# PDS_LogicConnections.net
KiCad netlist of a schematic drawn in Altium Designer
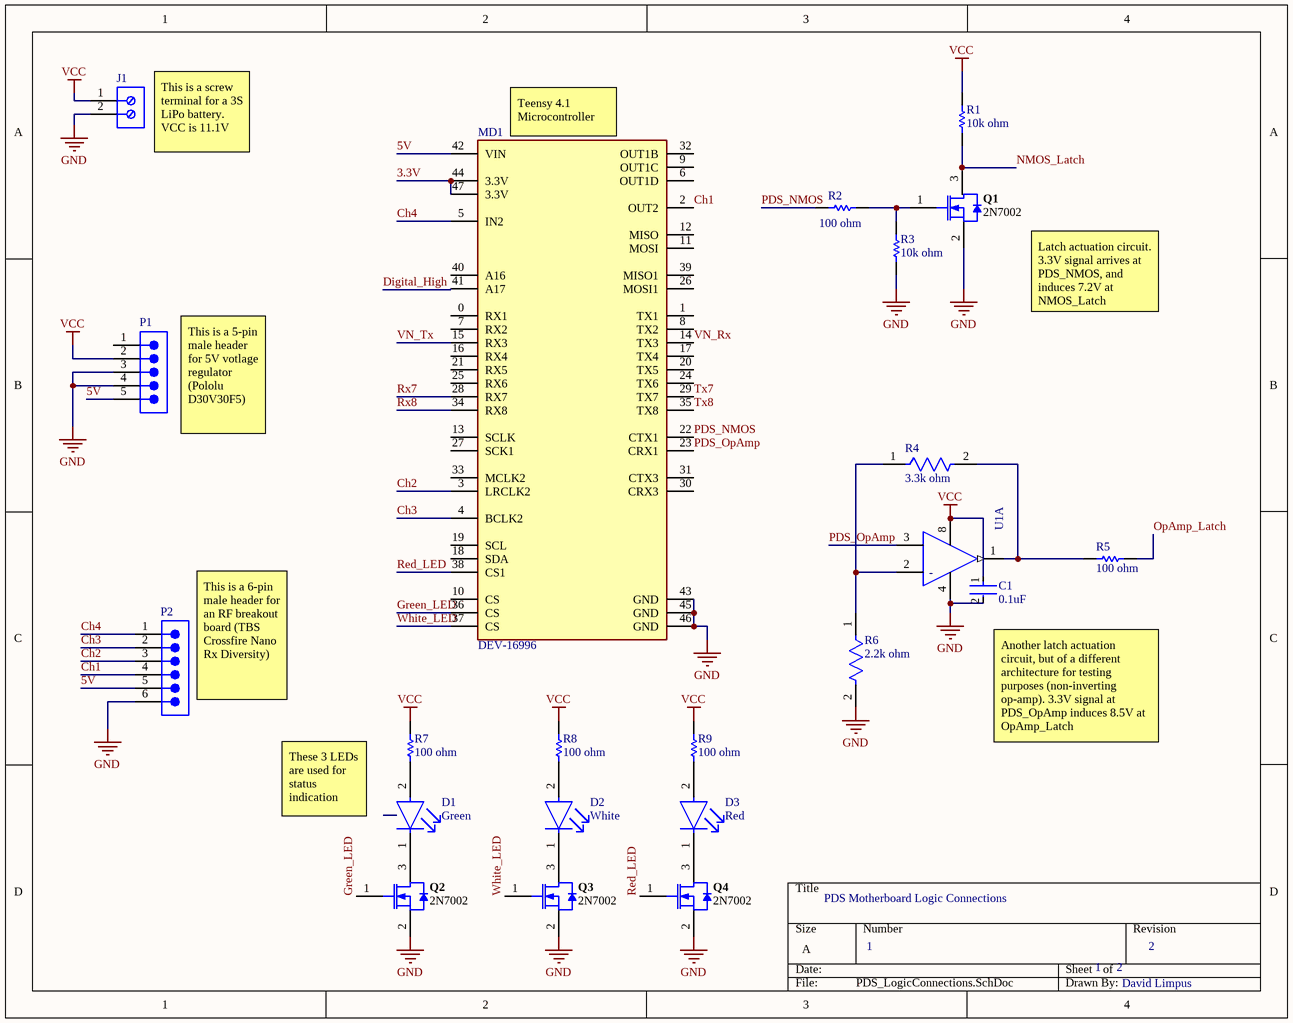
[diagram p0: PDS_LogicConnections.SchDoc]

(export (version "E")
  (design (tool "Eeschema 10.0.6"))
  (components
    (comp (ref "C1")
      (value "0.1uF")
      (footprint "FP-C0603C-CF-MFG")
      (description "CAP CER 0.1UF 50V X7R 0603")
      (fields (field (name "TOLERANCE") "0.1") (field (name "MANUFACTURER") "KEMET"))
      (libsource (lib "Altium Content Vault") (part "b4654b650e69147ec39a6b967a45e02"))
    )
    (comp (ref "D1")
      (value "Green")
      (footprint "FP-LTST-C190GKT-MFG")
      (description "LED GREEN CLEAR CHIP SMD")
      (fields (field (name "VOLTAGE") "2V"))
      (libsource (lib "Altium Content Vault") (part "8706943c75ba83719d021d2fdc84c58"))
    )
    (comp (ref "D2")
      (value "White")
      (footprint "FP-LTW-C191DS5-MFG")
      (description "LED WHITE CHIP SMD")
      (fields
        (field (name "OCTOPART") "https://octopart.com/ltw-c191ds5-lite-on-9287539")
        (field (name "MANUFACTURER PART NUMBER") "LTW-C191DS5")
      )
      (libsource (lib "Altium Content Vault") (part "8706943c75ba83719d021d2fdc84c58"))
    )
    (comp (ref "D3")
      (value "Red")
      (footprint "FP-LTST-C190EKT-MFG")
      (description "LED RED CLEAR CHIP SMD")
      (libsource (lib "Altium Content Vault") (part "8706943c75ba83719d021d2fdc84c58"))
    )
    (comp (ref "J1")
      (value "1725656")
      (footprint "PHOE-1725656-2")
      (description "Male Header, Pitch 2.54 mm, 1 x 2 Position, Height 9 mm, Tail Length 3.5 mm")
      (fields (field (name "MANUFACTURER") "Phoenix Contact"))
      (libsource (lib "Altium Content Vault") (part "CN-1P-F-TB2"))
    )
    (comp (ref "MD1")
      (value "DEV-16996")
      (footprint "FP-DEV-16996-MFG")
      (description "TEENSY 4.1 (HEADERS)")
      (libsource (lib "Altium Content Vault") (part "080115a1ce54750370cf87ec145ee29"))
    )
    (comp (ref "P1")
      (value "61300511121")
      (footprint "61300511121")
      (libsource (lib "Altium Content Vault") (part "Header_Male_1R_05P"))
    )
    (comp (ref "P2")
      (value "61300611121")
      (footprint "61300611121")
      (libsource (lib "Altium Content Vault") (part "Header_Male_1R_06P"))
    )
    (comp (ref "Q1")
      (value "2N7002")
      (footprint "INF-PG-SOT23_M")
      (fields (field (name "MANUFACTURER") "Infineon"))
      (libsource (lib "") (part "INF-NDMOS-GSD-3_1"))
    )
    (comp (ref "Q2")
      (value "2N7002")
      (footprint "INF-PG-SOT23_M")
      (fields (field (name "MANUFACTURER") "Infineon"))
      (libsource (lib "Altium Content Vault") (part "INF-NDMOS-GSD-3"))
    )
    (comp (ref "Q3")
      (value "2N7002")
      (footprint "INF-PG-SOT23_M")
      (fields (field (name "MANUFACTURER") "Infineon"))
      (libsource (lib "Altium Content Vault") (part "INF-NDMOS-GSD-3"))
    )
    (comp (ref "Q4")
      (value "2N7002")
      (footprint "INF-PG-SOT23_M")
      (fields (field (name "MANUFACTURER") "Infineon"))
      (libsource (lib "Altium Content Vault") (part "INF-NDMOS-GSD-3"))
    )
    (comp (ref "R1")
      (value "10k ohm")
      (footprint "RESC1609X50X30NL8T20")
      (description "Chip Resistor, 10 KOhm, +/- 1%, 100 mW, -55 to 155 degC, 0603 (1608 Metric), RoHS, Tape and Reel")
      (fields (field (name "MANUFACTURER") "Vishay Semiconductor"))
      (libsource (lib "Altium Content Vault") (part "RES-2"))
    )
    (comp (ref "R2")
      (value "100 ohm")
      (footprint "RESC1609X50X30ML8T20")
      (description "Chip Resistor, 100 Ohm, +/- 1%, 100 mW,-55 to 155 degC, 0603 (1608 Metric), RoHS, Tape and Ree")
      (fields (field (name "MANUFACTURER") "Vishay Semiconductor"))
      (libsource (lib "Altium Content Vault") (part "RES-2"))
    )
    (comp (ref "R3")
      (value "10k ohm")
      (footprint "RESC1609X50X30NL8T20")
      (description "Chip Resistor, 10 KOhm, +/- 1%, 100 mW, -55 to 155 degC, 0603 (1608 Metric), RoHS, Tape and Reel")
      (fields (field (name "MANUFACTURER") "Vishay Semiconductor"))
      (libsource (lib "Altium Content Vault") (part "RES-2"))
    )
    (comp (ref "R4")
      (value "3.3k ohm")
      (footprint "FP-RG1608-MFG")
      (description "Automotive Metal Thin Film Chip Resistor, 0603, 3.3kΩ, 0.1%, 25ppm/°C, 0.1W, 100V")
      (fields (field (name "TOLERANCE") "0.1%"))
      (libsource (lib "Altium Content Vault") (part "1029c3af85768c4190bb7ad29bc67b5"))
    )
    (comp (ref "R5")
      (value "100 ohm")
      (footprint "RESC1609X50X30ML8T20")
      (description "Chip Resistor, 100 Ohm, +/- 1%, 100 mW,-55 to 155 degC, 0603 (1608 Metric), RoHS, Tape and Ree")
      (fields (field (name "MANUFACTURER") "Vishay Semiconductor"))
      (libsource (lib "Altium Content Vault") (part "RES-2"))
    )
    (comp (ref "R6")
      (value "2.2k ohm")
      (footprint "FP-RT0603-MFG")
      (description "RES SMD 2.2K OHM 1% 1/10W 0603")
      (fields
        (field (name "MANUFACTURER") "Yageo")
        (field (name "OCTOPART") "https://octopart.com/rt0603fre072k2l-yageo-40019811")
      )
      (libsource (lib "Altium Content Vault") (part "1029c3af85768c4190bb7ad29bc67b5"))
    )
    (comp (ref "R7")
      (value "100 ohm")
      (footprint "RESC1609X50X30ML8T20")
      (description "Chip Resistor, 100 Ohm, +/- 1%, 100 mW,-55 to 155 degC, 0603 (1608 Metric), RoHS, Tape and Ree")
      (fields (field (name "MANUFACTURER") "Vishay Semiconductor"))
      (libsource (lib "Altium Content Vault") (part "RES-2"))
    )
    (comp (ref "R8")
      (value "100 ohm")
      (footprint "RESC1609X50X30ML8T20")
      (description "Chip Resistor, 100 Ohm, +/- 1%, 100 mW,-55 to 155 degC, 0603 (1608 Metric), RoHS, Tape and Ree")
      (fields (field (name "MANUFACTURER") "Vishay Semiconductor"))
      (libsource (lib "Altium Content Vault") (part "RES-2"))
    )
    (comp (ref "R9")
      (value "100 ohm")
      (footprint "RESC1609X50X30ML8T20")
      (description "Chip Resistor, 100 Ohm, +/- 1%, 100 mW,-55 to 155 degC, 0603 (1608 Metric), RoHS, Tape and Ree")
      (fields (field (name "MANUFACTURER") "Vishay Semiconductor"))
      (libsource (lib "Altium Content Vault") (part "RES-2"))
    )
    (comp (ref "U1")
      (value "LM358DR")
      (footprint "FP-D0008A-MFG")
      (description "IC OPAMP GP 2 CIRCUIT 8SOIC")
      (libsource (lib "Altium Content Vault") (part "0afdfe5f461d2cdd85604ff8654be97"))
    )
  )
  (nets
    (net (code "1") (name "/3.3V") (class "Default")
      (node (ref "MD1") (pin "44") (pinfunction "3.3V_44") (pintype "passive"))
      (node (ref "MD1") (pin "47") (pinfunction "3.3V_47") (pintype "passive"))
    )
    (net (code "2") (name "/5V") (class "Default")
      (node (ref "MD1") (pin "42") (pinfunction "VIN_42") (pintype "passive"))
      (node (ref "P1") (pin "5") (pinfunction "5_5") (pintype "passive"))
      (node (ref "P2") (pin "5") (pinfunction "5_5") (pintype "passive"))
    )
    (net (code "3") (name "/Ch1") (class "Default")
      (node (ref "MD1") (pin "2") (pinfunction "OUT2_2") (pintype "passive"))
      (node (ref "P2") (pin "4") (pinfunction "4_4") (pintype "passive"))
    )
    (net (code "4") (name "/Ch2") (class "Default")
      (node (ref "MD1") (pin "3") (pinfunction "LRCLK2_3") (pintype "passive"))
      (node (ref "P2") (pin "3") (pinfunction "3_3") (pintype "passive"))
    )
    (net (code "5") (name "/Ch3") (class "Default")
      (node (ref "MD1") (pin "4") (pinfunction "BCLK2_4") (pintype "passive"))
      (node (ref "P2") (pin "2") (pinfunction "2_2") (pintype "passive"))
    )
    (net (code "6") (name "/Ch4") (class "Default")
      (node (ref "MD1") (pin "5") (pinfunction "IN2_5") (pintype "passive"))
      (node (ref "P2") (pin "1") (pinfunction "1_1") (pintype "passive"))
    )
    (net (code "7") (name "/Digital_High") (class "Default")
      (node (ref "MD1") (pin "41") (pinfunction "A17_41") (pintype "passive"))
    )
    (net (code "8") (name "/Green_LED") (class "Default")
      (node (ref "MD1") (pin "36") (pinfunction "CS_36") (pintype "passive"))
      (node (ref "Q2") (pin "1") (pinfunction "GATE_1") (pintype "passive"))
    )
    (net (code "9") (name "/NMOS_Latch") (class "Default")
      (node (ref "Q1") (pin "3") (pinfunction "DRAIN_3") (pintype "passive"))
      (node (ref "R1") (pin "2") (pinfunction "2_2") (pintype "passive"))
    )
    (net (code "10") (name "/OpAmp_Latch") (class "Default")
      (node (ref "R5") (pin "2") (pinfunction "2_2") (pintype "passive"))
    )
    (net (code "11") (name "/PDS_NMOS") (class "Default")
      (node (ref "MD1") (pin "22") (pinfunction "CTX1_22") (pintype "passive"))
      (node (ref "R2") (pin "1") (pinfunction "1_1") (pintype "passive"))
    )
    (net (code "12") (name "/PDS_OpAmp") (class "Default")
      (node (ref "MD1") (pin "23") (pinfunction "CRX1_23") (pintype "passive"))
      (node (ref "U1") (pin "3") (pinfunction "IN1+_3") (pintype "tri_state"))
    )
    (net (code "13") (name "/Red_LED") (class "Default")
      (node (ref "MD1") (pin "38") (pinfunction "CS1_38") (pintype "passive"))
      (node (ref "Q4") (pin "1") (pinfunction "GATE_1") (pintype "passive"))
    )
    (net (code "14") (name "/Rx7") (class "Default")
      (node (ref "MD1") (pin "28") (pinfunction "RX7_28") (pintype "passive"))
    )
    (net (code "15") (name "/Rx8") (class "Default")
      (node (ref "MD1") (pin "34") (pinfunction "RX8_34") (pintype "passive"))
    )
    (net (code "16") (name "/Tx7") (class "Default")
      (node (ref "MD1") (pin "29") (pinfunction "TX7_29") (pintype "passive"))
    )
    (net (code "17") (name "/Tx8") (class "Default")
      (node (ref "MD1") (pin "35") (pinfunction "TX8_35") (pintype "passive"))
    )
    (net (code "18") (name "/VN_Rx") (class "Default")
      (node (ref "MD1") (pin "14") (pinfunction "TX3_14") (pintype "passive"))
    )
    (net (code "19") (name "/VN_Tx") (class "Default")
      (node (ref "MD1") (pin "15") (pinfunction "RX3_15") (pintype "passive"))
    )
    (net (code "20") (name "/White_LED") (class "Default")
      (node (ref "MD1") (pin "37") (pinfunction "CS_37") (pintype "passive"))
      (node (ref "Q3") (pin "1") (pinfunction "GATE_1") (pintype "passive"))
    )
    (net (code "21") (name "GND") (class "Default")
      (node (ref "C1") (pin "2") (pinfunction "2_2") (pintype "passive"))
      (node (ref "J1") (pin "2") (pinfunction "2_2") (pintype "passive"))
      (node (ref "MD1") (pin "43") (pinfunction "GND_43") (pintype "passive"))
      (node (ref "MD1") (pin "45") (pinfunction "GND_45") (pintype "passive"))
      (node (ref "MD1") (pin "46") (pinfunction "GND_46") (pintype "passive"))
      (node (ref "P1") (pin "3") (pinfunction "3_3") (pintype "passive"))
      (node (ref "P1") (pin "4") (pinfunction "4_4") (pintype "passive"))
      (node (ref "P2") (pin "6") (pinfunction "6_6") (pintype "passive"))
      (node (ref "Q1") (pin "2") (pinfunction "SOURCE_2") (pintype "passive"))
      (node (ref "Q2") (pin "2") (pinfunction "SOURCE_2") (pintype "passive"))
      (node (ref "Q3") (pin "2") (pinfunction "SOURCE_2") (pintype "passive"))
      (node (ref "Q4") (pin "2") (pinfunction "SOURCE_2") (pintype "passive"))
      (node (ref "R3") (pin "2") (pinfunction "2_2") (pintype "passive"))
      (node (ref "R6") (pin "2") (pinfunction "2_2") (pintype "passive"))
      (node (ref "U1") (pin "4") (pinfunction "V-_4") (pintype "power_in"))
    )
    (net (code "22") (name "Net-(D1-A)") (class "Default")
      (node (ref "D1") (pin "2") (pinfunction "A_2") (pintype "passive"))
      (node (ref "R7") (pin "2") (pinfunction "2_2") (pintype "passive"))
    )
    (net (code "23") (name "Net-(D1-C)") (class "Default")
      (node (ref "D1") (pin "1") (pinfunction "C_1") (pintype "passive"))
      (node (ref "Q2") (pin "3") (pinfunction "DRAIN_3") (pintype "passive"))
    )
    (net (code "24") (name "Net-(D2-A)") (class "Default")
      (node (ref "D2") (pin "2") (pinfunction "A_2") (pintype "passive"))
      (node (ref "R8") (pin "2") (pinfunction "2_2") (pintype "passive"))
    )
    (net (code "25") (name "Net-(D2-C)") (class "Default")
      (node (ref "D2") (pin "1") (pinfunction "C_1") (pintype "passive"))
      (node (ref "Q3") (pin "3") (pinfunction "DRAIN_3") (pintype "passive"))
    )
    (net (code "26") (name "Net-(D3-A)") (class "Default")
      (node (ref "D3") (pin "2") (pinfunction "A_2") (pintype "passive"))
      (node (ref "R9") (pin "2") (pinfunction "2_2") (pintype "passive"))
    )
    (net (code "27") (name "Net-(D3-C)") (class "Default")
      (node (ref "D3") (pin "1") (pinfunction "C_1") (pintype "passive"))
      (node (ref "Q4") (pin "3") (pinfunction "DRAIN_3") (pintype "passive"))
    )
    (net (code "28") (name "Net-(Q1-GATE)") (class "Default")
      (node (ref "Q1") (pin "1") (pinfunction "GATE_1") (pintype "passive"))
      (node (ref "R2") (pin "2") (pinfunction "2_2") (pintype "passive"))
      (node (ref "R3") (pin "1") (pinfunction "1_1") (pintype "passive"))
    )
    (net (code "29") (name "Net-(U1A-1OUT)") (class "Default")
      (node (ref "R4") (pin "2") (pinfunction "2_2") (pintype "passive"))
      (node (ref "R5") (pin "1") (pinfunction "1_1") (pintype "passive"))
      (node (ref "U1") (pin "1") (pinfunction "1OUT_1") (pintype "output"))
    )
    (net (code "30") (name "Net-(U1A-IN1-)") (class "Default")
      (node (ref "R4") (pin "1") (pinfunction "1_1") (pintype "passive"))
      (node (ref "R6") (pin "1") (pinfunction "1_1") (pintype "passive"))
      (node (ref "U1") (pin "2") (pinfunction "IN1-_2") (pintype "tri_state"))
    )
    (net (code "31") (name "VCC") (class "Default")
      (node (ref "C1") (pin "1") (pinfunction "1_1") (pintype "passive"))
      (node (ref "J1") (pin "1") (pinfunction "1_1") (pintype "passive"))
      (node (ref "P1") (pin "2") (pinfunction "2_2") (pintype "passive"))
      (node (ref "R1") (pin "1") (pinfunction "1_1") (pintype "passive"))
      (node (ref "R7") (pin "1") (pinfunction "1_1") (pintype "passive"))
      (node (ref "R8") (pin "1") (pinfunction "1_1") (pintype "passive"))
      (node (ref "R9") (pin "1") (pinfunction "1_1") (pintype "passive"))
      (node (ref "U1") (pin "8") (pinfunction "V+_8") (pintype "power_in"))
    )
    (net (code "32") (name "unconnected-(MD1-A16-Pad40)") (class "Default")
      (node (ref "MD1") (pin "40") (pinfunction "A16_40") (pintype "passive"))
    )
    (net (code "33") (name "unconnected-(MD1-CRX3-Pad30)") (class "Default")
      (node (ref "MD1") (pin "30") (pinfunction "CRX3_30") (pintype "passive"))
    )
    (net (code "34") (name "unconnected-(MD1-CS-Pad10)") (class "Default")
      (node (ref "MD1") (pin "10") (pinfunction "CS_10") (pintype "passive"))
    )
    (net (code "35") (name "unconnected-(MD1-CTX3-Pad31)") (class "Default")
      (node (ref "MD1") (pin "31") (pinfunction "CTX3_31") (pintype "passive"))
    )
    (net (code "36") (name "unconnected-(MD1-MCLK2-Pad33)") (class "Default")
      (node (ref "MD1") (pin "33") (pinfunction "MCLK2_33") (pintype "passive"))
    )
    (net (code "37") (name "unconnected-(MD1-MISO-Pad12)") (class "Default")
      (node (ref "MD1") (pin "12") (pinfunction "MISO_12") (pintype "passive"))
    )
    (net (code "38") (name "unconnected-(MD1-MISO1-Pad39)") (class "Default")
      (node (ref "MD1") (pin "39") (pinfunction "MISO1_39") (pintype "passive"))
    )
    (net (code "39") (name "unconnected-(MD1-MOSI-Pad11)") (class "Default")
      (node (ref "MD1") (pin "11") (pinfunction "MOSI_11") (pintype "passive"))
    )
    (net (code "40") (name "unconnected-(MD1-MOSI1-Pad26)") (class "Default")
      (node (ref "MD1") (pin "26") (pinfunction "MOSI1_26") (pintype "passive"))
    )
    (net (code "41") (name "unconnected-(MD1-OUT1B-Pad32)") (class "Default")
      (node (ref "MD1") (pin "32") (pinfunction "OUT1B_32") (pintype "passive"))
    )
    (net (code "42") (name "unconnected-(MD1-OUT1C-Pad9)") (class "Default")
      (node (ref "MD1") (pin "9") (pinfunction "OUT1C_9") (pintype "passive"))
    )
    (net (code "43") (name "unconnected-(MD1-OUT1D-Pad6)") (class "Default")
      (node (ref "MD1") (pin "6") (pinfunction "OUT1D_6") (pintype "passive"))
    )
    (net (code "44") (name "unconnected-(MD1-RX1-Pad0)") (class "Default")
      (node (ref "MD1") (pin "0") (pinfunction "RX1_0") (pintype "passive"))
    )
    (net (code "45") (name "unconnected-(MD1-RX2-Pad7)") (class "Default")
      (node (ref "MD1") (pin "7") (pinfunction "RX2_7") (pintype "passive"))
    )
    (net (code "46") (name "unconnected-(MD1-RX4-Pad16)") (class "Default")
      (node (ref "MD1") (pin "16") (pinfunction "RX4_16") (pintype "passive"))
    )
    (net (code "47") (name "unconnected-(MD1-RX5-Pad21)") (class "Default")
      (node (ref "MD1") (pin "21") (pinfunction "RX5_21") (pintype "passive"))
    )
    (net (code "48") (name "unconnected-(MD1-RX6-Pad25)") (class "Default")
      (node (ref "MD1") (pin "25") (pinfunction "RX6_25") (pintype "passive"))
    )
    (net (code "49") (name "unconnected-(MD1-SCK1-Pad27)") (class "Default")
      (node (ref "MD1") (pin "27") (pinfunction "SCK1_27") (pintype "passive"))
    )
    (net (code "50") (name "unconnected-(MD1-SCL-Pad19)") (class "Default")
      (node (ref "MD1") (pin "19") (pinfunction "SCL_19") (pintype "passive"))
    )
    (net (code "51") (name "unconnected-(MD1-SCLK-Pad13)") (class "Default")
      (node (ref "MD1") (pin "13") (pinfunction "SCLK_13") (pintype "passive"))
    )
    (net (code "52") (name "unconnected-(MD1-SDA-Pad18)") (class "Default")
      (node (ref "MD1") (pin "18") (pinfunction "SDA_18") (pintype "passive"))
    )
    (net (code "53") (name "unconnected-(MD1-TX1-Pad1)") (class "Default")
      (node (ref "MD1") (pin "1") (pinfunction "TX1_1") (pintype "passive"))
    )
    (net (code "54") (name "unconnected-(MD1-TX2-Pad8)") (class "Default")
      (node (ref "MD1") (pin "8") (pinfunction "TX2_8") (pintype "passive"))
    )
    (net (code "55") (name "unconnected-(MD1-TX4-Pad17)") (class "Default")
      (node (ref "MD1") (pin "17") (pinfunction "TX4_17") (pintype "passive"))
    )
    (net (code "56") (name "unconnected-(MD1-TX5-Pad20)") (class "Default")
      (node (ref "MD1") (pin "20") (pinfunction "TX5_20") (pintype "passive"))
    )
    (net (code "57") (name "unconnected-(MD1-TX6-Pad24)") (class "Default")
      (node (ref "MD1") (pin "24") (pinfunction "TX6_24") (pintype "passive"))
    )
    (net (code "58") (name "unconnected-(P1-Pad1)") (class "Default")
      (node (ref "P1") (pin "1") (pinfunction "1_1") (pintype "passive"))
    )
  )
)
